# untitled.net
KiCad netlist of a schematic drawn in EAGLE
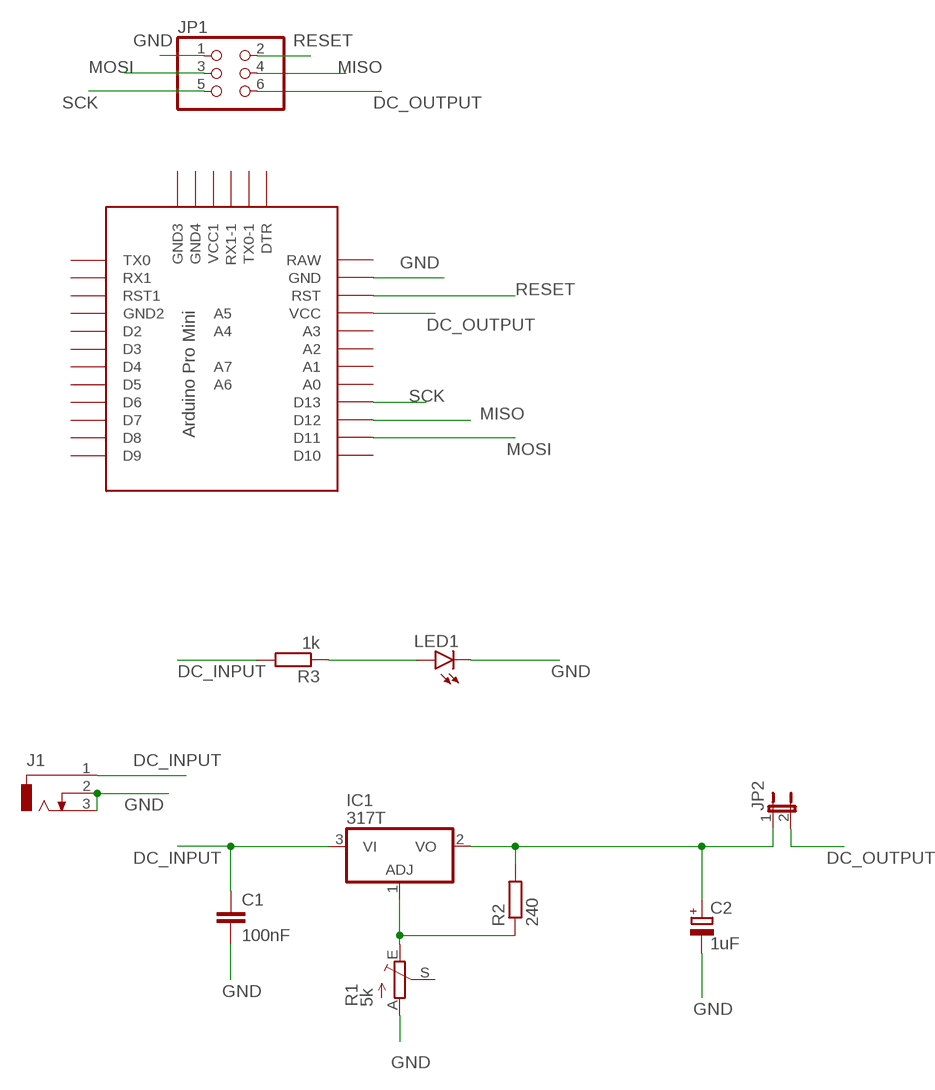
[diagram p0: schematic, sheet 1]

(export (version "E")
  (design (tool "Eeschema 10.0.6"))
  (components
    (comp (ref "C1")
      (value "100nF")
      (footprint "eagle-import:C025-025X050")
      (libsource (lib "eagle-import") (part "C-EU025-025X050"))
    )
    (comp (ref "C2")
      (value "1uF")
      (footprint "eagle-import:E2,5-5")
      (libsource (lib "eagle-import") (part "CPOL-EUE2.5-5"))
    )
    (comp (ref "IC1")
      (value "317T")
      (footprint "eagle-import:TO220H")
      (libsource (lib "eagle-import") (part "317T"))
    )
    (comp (ref "J1")
      (value "DCJ0303")
      (footprint "eagle-import:DCJ0303")
      (libsource (lib "eagle-import") (part "DCJ0303"))
    )
    (comp (ref "JP1")
      (value "PINHD-2X3")
      (footprint "eagle-import:2X03")
      (libsource (lib "eagle-import") (part "PINHD-2X3"))
    )
    (comp (ref "JP2")
      (value "JP1E")
      (footprint "eagle-import:JP1")
      (libsource (lib "eagle-import") (part "JP1E"))
    )
    (comp (ref "LED1")
      (value "LED5MM")
      (footprint "eagle-import:LED5MM")
      (libsource (lib "eagle-import") (part "LED5MM"))
    )
    (comp (ref "R1")
      (value "5k")
      (footprint "eagle-import:S64YW")
      (libsource (lib "eagle-import") (part "TRIM_1234-S64YW"))
    )
    (comp (ref "R2")
      (value "240")
      (footprint "eagle-import:0204_5")
      (libsource (lib "eagle-import") (part "R-EU_0204/5"))
    )
    (comp (ref "R3")
      (value "1k")
      (footprint "eagle-import:0204_5")
      (libsource (lib "eagle-import") (part "R-EU_0204/5"))
    )
    (comp (ref "U$1")
      (value "PRO-MINI-2")
      (footprint "eagle-import:PRO-MINI-2")
      (libsource (lib "eagle-import") (part "PRO-MINI-2"))
    )
  )
  (nets
    (net (code "1") (name "/DC_INPUT") (class "Default")
      (node (ref "C1") (pin "1") (pinfunction "1_1") (pintype "passive"))
      (node (ref "IC1") (pin "3") (pinfunction "VI_3") (pintype "input"))
      (node (ref "J1") (pin "1") (pinfunction "1_1") (pintype "passive"))
      (node (ref "R3") (pin "2") (pinfunction "2_2") (pintype "passive"))
    )
    (net (code "2") (name "/DC_OUTPUT") (class "Default")
      (node (ref "JP1") (pin "6") (pinfunction "6_6") (pintype "passive"))
      (node (ref "JP2") (pin "2") (pinfunction "2_2") (pintype "passive"))
      (node (ref "U$1") (pin "VCC") (pinfunction "VCC_VCC") (pintype "bidirectional"))
    )
    (net (code "3") (name "/GND") (class "Default")
      (node (ref "C1") (pin "2") (pinfunction "2_2") (pintype "passive"))
      (node (ref "C2") (pin "-") (pinfunction "-_-") (pintype "passive"))
      (node (ref "J1") (pin "2") (pinfunction "2_2") (pintype "passive"))
      (node (ref "J1") (pin "3") (pinfunction "3_3") (pintype "passive"))
      (node (ref "JP1") (pin "1") (pinfunction "1_1") (pintype "passive"))
      (node (ref "LED1") (pin "K") (pinfunction "C_K") (pintype "passive"))
      (node (ref "R1") (pin "A") (pinfunction "A_A") (pintype "passive"))
      (node (ref "U$1") (pin "GND") (pinfunction "GND_GND") (pintype "bidirectional"))
    )
    (net (code "4") (name "/MISO") (class "Default")
      (node (ref "JP1") (pin "4") (pinfunction "4_4") (pintype "passive"))
      (node (ref "U$1") (pin "D12") (pinfunction "D12_D12") (pintype "bidirectional"))
    )
    (net (code "5") (name "/MOSI") (class "Default")
      (node (ref "JP1") (pin "3") (pinfunction "3_3") (pintype "passive"))
      (node (ref "U$1") (pin "D11") (pinfunction "D11_D11") (pintype "bidirectional"))
    )
    (net (code "6") (name "/RESET") (class "Default")
      (node (ref "JP1") (pin "2") (pinfunction "2_2") (pintype "passive"))
      (node (ref "U$1") (pin "RST") (pinfunction "RST_RST") (pintype "bidirectional"))
    )
    (net (code "7") (name "/SCK") (class "Default")
      (node (ref "JP1") (pin "5") (pinfunction "5_5") (pintype "passive"))
      (node (ref "U$1") (pin "D13") (pinfunction "D13_D13") (pintype "bidirectional"))
    )
    (net (code "8") (name "Net-(IC1-ADJ)") (class "Default")
      (node (ref "IC1") (pin "1") (pinfunction "ADJ_1") (pintype "input"))
      (node (ref "R1") (pin "E") (pinfunction "E_E") (pintype "passive"))
      (node (ref "R2") (pin "1") (pinfunction "1_1") (pintype "passive"))
    )
    (net (code "9") (name "Net-(IC1-VO)") (class "Default")
      (node (ref "C2") (pin "+") (pinfunction "+_+") (pintype "passive"))
      (node (ref "IC1") (pin "2") (pinfunction "VO_2") (pintype "passive"))
      (node (ref "JP2") (pin "1") (pinfunction "1_1") (pintype "passive"))
      (node (ref "R2") (pin "2") (pinfunction "2_2") (pintype "passive"))
    )
    (net (code "10") (name "Net-(LED1-PadA)") (class "Default")
      (node (ref "LED1") (pin "A") (pinfunction "A_A") (pintype "passive"))
      (node (ref "R3") (pin "1") (pinfunction "1_1") (pintype "passive"))
    )
    (net (code "11") (name "unconnected-(R1-PadS)") (class "Default")
      (node (ref "R1") (pin "S") (pinfunction "S_S") (pintype "passive"))
    )
    (net (code "12") (name "unconnected-(R1-S-PadS@1)") (class "Default")
      (node (ref "R1") (pin "S@1") (pinfunction "S_S@1") (pintype "passive"))
    )
    (net (code "13") (name "unconnected-(U$1-GND2-PadGND1)") (class "Default")
      (node (ref "U$1") (pin "GND1") (pinfunction "GND2_GND1") (pintype "bidirectional"))
    )
    (net (code "14") (name "unconnected-(U$1-GND3-PadGND2)") (class "Default")
      (node (ref "U$1") (pin "GND2") (pinfunction "GND3_GND2") (pintype "bidirectional"))
    )
    (net (code "15") (name "unconnected-(U$1-GND4-PadGND3)") (class "Default")
      (node (ref "U$1") (pin "GND3") (pinfunction "GND4_GND3") (pintype "bidirectional"))
    )
    (net (code "16") (name "unconnected-(U$1-PadA0)") (class "Default")
      (node (ref "U$1") (pin "A0") (pinfunction "A0_A0") (pintype "bidirectional"))
    )
    (net (code "17") (name "unconnected-(U$1-PadA1)") (class "Default")
      (node (ref "U$1") (pin "A1") (pinfunction "A1_A1") (pintype "bidirectional"))
    )
    (net (code "18") (name "unconnected-(U$1-PadA2)") (class "Default")
      (node (ref "U$1") (pin "A2") (pinfunction "A2_A2") (pintype "bidirectional"))
    )
    (net (code "19") (name "unconnected-(U$1-PadA3)") (class "Default")
      (node (ref "U$1") (pin "A3") (pinfunction "A3_A3") (pintype "bidirectional"))
    )
    (net (code "20") (name "unconnected-(U$1-PadA4)") (class "Default")
      (node (ref "U$1") (pin "A4") (pinfunction "A4_A4") (pintype "bidirectional"))
    )
    (net (code "21") (name "unconnected-(U$1-PadA5)") (class "Default")
      (node (ref "U$1") (pin "A5") (pinfunction "A5_A5") (pintype "bidirectional"))
    )
    (net (code "22") (name "unconnected-(U$1-PadA6)") (class "Default")
      (node (ref "U$1") (pin "A6") (pinfunction "A6_A6") (pintype "bidirectional"))
    )
    (net (code "23") (name "unconnected-(U$1-PadA7)") (class "Default")
      (node (ref "U$1") (pin "A7") (pinfunction "A7_A7") (pintype "bidirectional"))
    )
    (net (code "24") (name "unconnected-(U$1-PadD2)") (class "Default")
      (node (ref "U$1") (pin "D2") (pinfunction "D2_D2") (pintype "bidirectional"))
    )
    (net (code "25") (name "unconnected-(U$1-PadD3)") (class "Default")
      (node (ref "U$1") (pin "D3") (pinfunction "D3_D3") (pintype "bidirectional"))
    )
    (net (code "26") (name "unconnected-(U$1-PadD4)") (class "Default")
      (node (ref "U$1") (pin "D4") (pinfunction "D4_D4") (pintype "bidirectional"))
    )
    (net (code "27") (name "unconnected-(U$1-PadD5)") (class "Default")
      (node (ref "U$1") (pin "D5") (pinfunction "D5_D5") (pintype "bidirectional"))
    )
    (net (code "28") (name "unconnected-(U$1-PadD6)") (class "Default")
      (node (ref "U$1") (pin "D6") (pinfunction "D6_D6") (pintype "bidirectional"))
    )
    (net (code "29") (name "unconnected-(U$1-PadD7)") (class "Default")
      (node (ref "U$1") (pin "D7") (pinfunction "D7_D7") (pintype "bidirectional"))
    )
    (net (code "30") (name "unconnected-(U$1-PadD8)") (class "Default")
      (node (ref "U$1") (pin "D8") (pinfunction "D8_D8") (pintype "bidirectional"))
    )
    (net (code "31") (name "unconnected-(U$1-PadD9)") (class "Default")
      (node (ref "U$1") (pin "D9") (pinfunction "D9_D9") (pintype "bidirectional"))
    )
    (net (code "32") (name "unconnected-(U$1-PadD10)") (class "Default")
      (node (ref "U$1") (pin "D10") (pinfunction "D10_D10") (pintype "bidirectional"))
    )
    (net (code "33") (name "unconnected-(U$1-PadDTR)") (class "Default")
      (node (ref "U$1") (pin "DTR") (pinfunction "DTR_DTR") (pintype "bidirectional"))
    )
    (net (code "34") (name "unconnected-(U$1-PadRAW)") (class "Default")
      (node (ref "U$1") (pin "RAW") (pinfunction "RAW_RAW") (pintype "bidirectional"))
    )
    (net (code "35") (name "unconnected-(U$1-PadRST1)") (class "Default")
      (node (ref "U$1") (pin "RST1") (pinfunction "RST1_RST1") (pintype "bidirectional"))
    )
    (net (code "36") (name "unconnected-(U$1-PadRX1)") (class "Default")
      (node (ref "U$1") (pin "RX1") (pinfunction "RX1_RX1") (pintype "bidirectional"))
    )
    (net (code "37") (name "unconnected-(U$1-PadRX1-1)") (class "Default")
      (node (ref "U$1") (pin "RX1-1") (pinfunction "RX1-1_RX1-1") (pintype "bidirectional"))
    )
    (net (code "38") (name "unconnected-(U$1-PadTX0)") (class "Default")
      (node (ref "U$1") (pin "TX0") (pinfunction "TX0_TX0") (pintype "bidirectional"))
    )
    (net (code "39") (name "unconnected-(U$1-PadTX0-1)") (class "Default")
      (node (ref "U$1") (pin "TX0-1") (pinfunction "TX0-1_TX0-1") (pintype "bidirectional"))
    )
    (net (code "40") (name "unconnected-(U$1-PadVCC1)") (class "Default")
      (node (ref "U$1") (pin "VCC1") (pinfunction "VCC1_VCC1") (pintype "bidirectional"))
    )
  )
)
